# Sheet2.net
KiCad netlist of a schematic drawn in Altium Designer
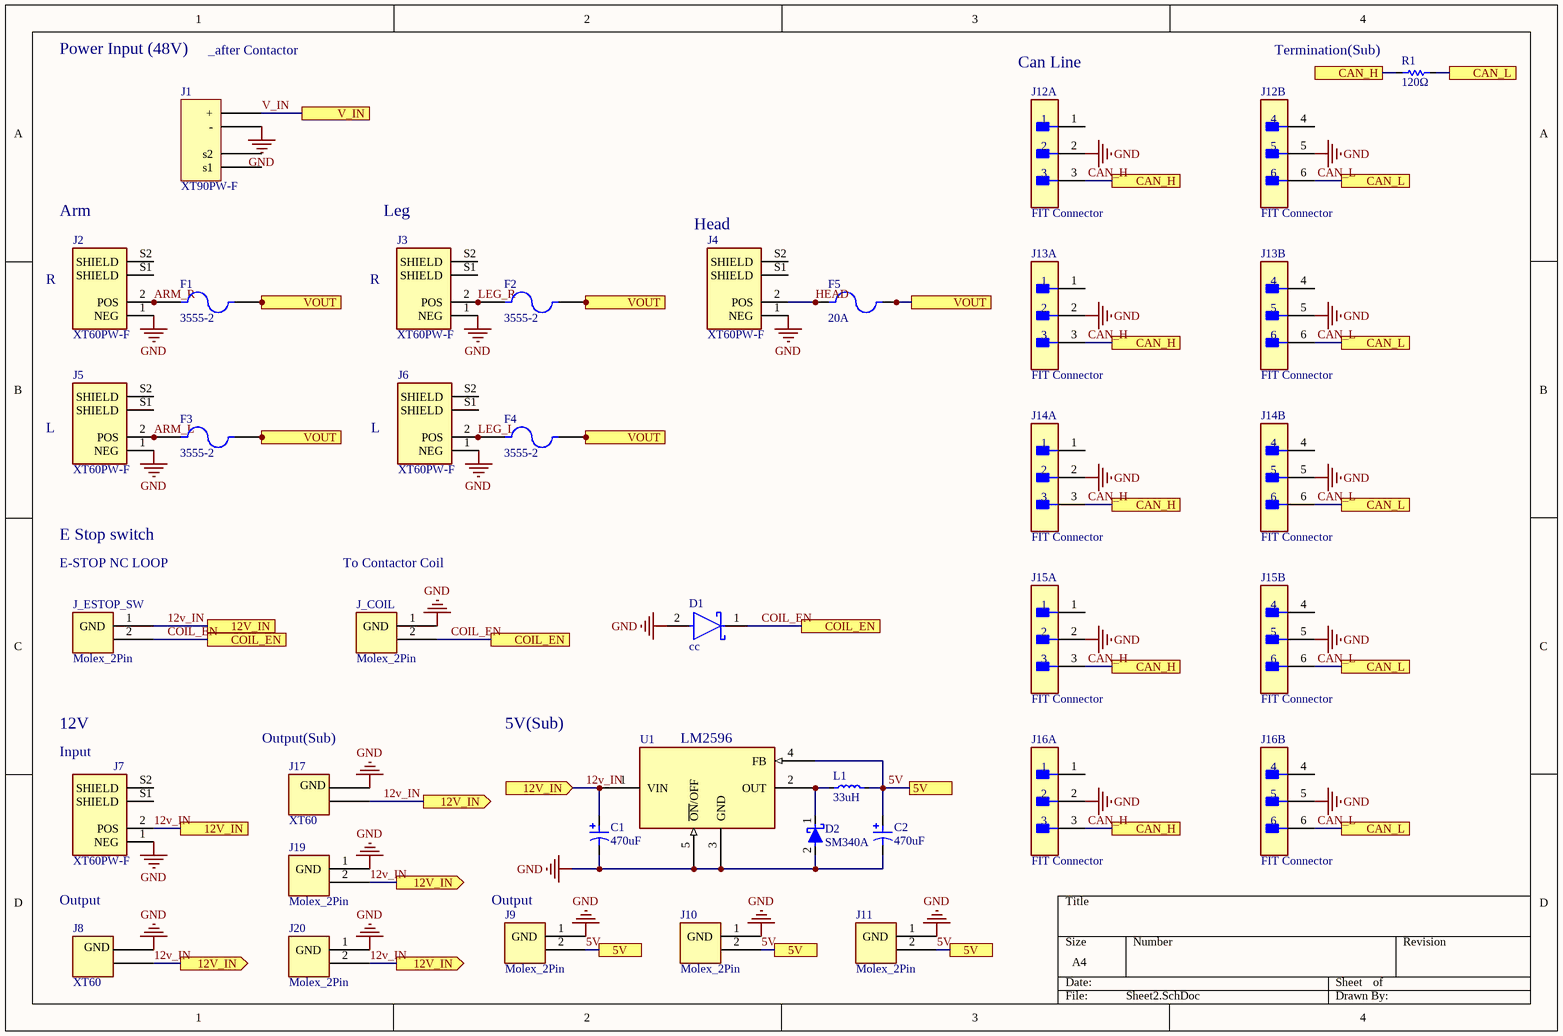
[diagram p0: Sheet2.SchDoc]

(export (version "E")
  (design (tool "Eeschema 10.0.6"))
  (components
    (comp (ref "C1")
      (value "Polar_Capacitors")
      (footprint "SMD_Capacitor_electrolytic")
      (description "Electrolytic Capacitor")
      (fields (field (name "CAPACITANCE") "470uF") (field (name "SOURCE") "robit_passive.SchLib"))
      (libsource (lib "robit circuit") (part "Capacitor_electrolytic"))
    )
    (comp (ref "C2")
      (value "Polar_Capacitors")
      (footprint "SMD_Capacitor_electrolytic")
      (description "Electrolytic Capacitor")
      (fields (field (name "CAPACITANCE") "470uF") (field (name "SOURCE") "robit_passive.SchLib"))
      (libsource (lib "robit circuit") (part "Capacitor_electrolytic"))
    )
    (comp (ref "D1")
      (value "cc")
      (footprint "FP-403A-03-MFG")
      (description "Rectifier Diode, Schottky, 1 Phase, 1 Element, 5A, 100V V(RRM), Silicon")
      (libsource (lib "robit circuit") (part "1d6ec82d83fb6aee721767c19dac4b9"))
    )
    (comp (ref "D2")
      (value "SM340A")
      (footprint "SMD_Diode_schottky")
      (description "Schottky Barrier Diode")
      (fields (field (name "SOURCE") "robit_passive.SchLib"))
      (libsource (lib "robit circuit") (part "Diode_schottky"))
    )
    (comp (ref "F1")
      (value "3555-2")
      (footprint "FUSE_3555-2")
      (fields (field (name "MF") "Keystone Electronics"))
      (libsource (lib "3555-2 (1)") (part "3555-2"))
    )
    (comp (ref "F2")
      (value "3555-2")
      (footprint "FUSE_3555-2")
      (fields (field (name "MF") "Keystone Electronics"))
      (libsource (lib "3555-2 (1)") (part "3555-2"))
    )
    (comp (ref "F3")
      (value "3555-2")
      (footprint "FUSE_3555-2")
      (fields (field (name "MF") "Keystone Electronics"))
      (libsource (lib "3555-2 (1)") (part "3555-2"))
    )
    (comp (ref "F4")
      (value "3555-2")
      (footprint "FUSE_3555-2")
      (fields (field (name "MF") "Keystone Electronics"))
      (libsource (lib "3555-2 (1)") (part "3555-2"))
    )
    (comp (ref "F5")
      (value "20A")
      (footprint "FUSE_CNX-02")
      (description "Fuse Clip for Maxi Blade Fuse, 250VDC/500VAC, 80A")
      (fields (field (name "MF") "OptiFuse") (field (name "MP") "CNX-02"))
      (libsource (lib "robit circuit") (part "CNX-02"))
    )
    (comp (ref "J1")
      (value "XT90PW-F")
      (footprint "AMASS_XT90PW-F")
      (description "Socket, DC supply, XT90, female, PIN:2, on PCBs, THT")
      (fields (field (name "MF") "AMASS"))
      (libsource (lib "robit circuit") (part "XT90PW-F"))
    )
    (comp (ref "J2")
      (value "XT60PW-F")
      (footprint "XT60PW-F")
      (description "Socket DC Supply Connector Female")
      (fields (field (name "MF") "AMASS") (field (name "SOURCE") "robit_connector.SchLib"))
      (libsource (lib "robit circuit") (part "XT60PW-F"))
    )
    (comp (ref "J3")
      (value "XT60PW-F")
      (footprint "XT60PW-F")
      (description "Socket DC Supply Connector Female")
      (fields (field (name "MF") "AMASS") (field (name "SOURCE") "robit_connector.SchLib"))
      (libsource (lib "robit circuit") (part "XT60PW-F"))
    )
    (comp (ref "J4")
      (value "XT60PW-F")
      (footprint "XT60PW-F")
      (description "Socket DC Supply Connector Female")
      (fields (field (name "MF") "AMASS") (field (name "SOURCE") "robit_connector.SchLib"))
      (libsource (lib "robit circuit") (part "XT60PW-F"))
    )
    (comp (ref "J5")
      (value "XT60PW-F")
      (footprint "XT60PW-F")
      (description "Socket DC Supply Connector Female")
      (fields (field (name "MF") "AMASS") (field (name "SOURCE") "robit_connector.SchLib"))
      (libsource (lib "robit circuit") (part "XT60PW-F"))
    )
    (comp (ref "J6")
      (value "XT60PW-F")
      (footprint "XT60PW-F")
      (description "Socket DC Supply Connector Female")
      (fields (field (name "MF") "AMASS") (field (name "SOURCE") "robit_connector.SchLib"))
      (libsource (lib "robit circuit") (part "XT60PW-F"))
    )
    (comp (ref "J7")
      (value "XT60PW-F")
      (footprint "XT60PW-F")
      (description "Socket DC Supply Connector Female")
      (fields (field (name "MF") "AMASS") (field (name "SOURCE") "robit_connector.SchLib"))
      (libsource (lib "robit circuit") (part "XT60PW-F"))
    )
    (comp (ref "J8")
      (value "XT60")
      (footprint "XT60_F")
      (description "XT60 connector")
      (libsource (lib "robit circuit") (part "XT60"))
    )
    (comp (ref "J9")
      (value "Molex_2Pin")
      (footprint "MOLEX_2PIN")
      (description "Molex 2Pin Connector")
      (fields (field (name "SOURCE") "robit_connector.SchLib"))
      (libsource (lib "robit circuit") (part "Molex_2Pin"))
    )
    (comp (ref "J10")
      (value "Molex_2Pin")
      (footprint "MOLEX_2PIN")
      (description "Molex 2Pin Connector")
      (fields (field (name "SOURCE") "robit_connector.SchLib"))
      (libsource (lib "robit circuit") (part "Molex_2Pin"))
    )
    (comp (ref "J11")
      (value "Molex_2Pin")
      (footprint "MOLEX_2PIN")
      (description "Molex 2Pin Connector")
      (fields (field (name "SOURCE") "robit_connector.SchLib"))
      (libsource (lib "robit circuit") (part "Molex_2Pin"))
    )
    (comp (ref "J12")
      (value "FIT Connector")
      (footprint "FP-43045-0601-MFG")
      (description "Connector Wire to Board Header 6 Position 3 mm Solder Right Angle Thru-Hole Micro-Fit 3.0™")
      (libsource (lib "robit circuit") (part "7bb5f7ddfb2bec276e641070710345c"))
    )
    (comp (ref "J13")
      (value "FIT Connector")
      (footprint "FP-43045-0601-MFG")
      (description "Connector Wire to Board Header 6 Position 3 mm Solder Right Angle Thru-Hole Micro-Fit 3.0™")
      (libsource (lib "robit circuit") (part "7bb5f7ddfb2bec276e641070710345c"))
    )
    (comp (ref "J14")
      (value "FIT Connector")
      (footprint "FP-43045-0601-MFG")
      (description "Connector Wire to Board Header 6 Position 3 mm Solder Right Angle Thru-Hole Micro-Fit 3.0™")
      (libsource (lib "robit circuit") (part "7bb5f7ddfb2bec276e641070710345c"))
    )
    (comp (ref "J15")
      (value "FIT Connector")
      (footprint "FP-43045-0601-MFG")
      (description "Connector Wire to Board Header 6 Position 3 mm Solder Right Angle Thru-Hole Micro-Fit 3.0™")
      (libsource (lib "robit circuit") (part "7bb5f7ddfb2bec276e641070710345c"))
    )
    (comp (ref "J16")
      (value "FIT Connector")
      (footprint "FP-43045-0601-MFG")
      (description "Connector Wire to Board Header 6 Position 3 mm Solder Right Angle Thru-Hole Micro-Fit 3.0™")
      (libsource (lib "robit circuit") (part "7bb5f7ddfb2bec276e641070710345c"))
    )
    (comp (ref "J17")
      (value "XT60")
      (footprint "XT60_F")
      (description "XT60 connector")
      (libsource (lib "robit circuit") (part "XT60"))
    )
    (comp (ref "J19")
      (value "Molex_2Pin")
      (footprint "MOLEX_2PIN")
      (description "Molex 2Pin Connector")
      (fields (field (name "SOURCE") "robit_connector.SchLib"))
      (libsource (lib "robit circuit") (part "Molex_2Pin"))
    )
    (comp (ref "J20")
      (value "Molex_2Pin")
      (footprint "MOLEX_2PIN")
      (description "Molex 2Pin Connector")
      (fields (field (name "SOURCE") "robit_connector.SchLib"))
      (libsource (lib "robit circuit") (part "Molex_2Pin"))
    )
    (comp (ref "J_COIL")
      (value "Molex_2Pin")
      (footprint "MOLEX_2PIN")
      (description "Molex 2Pin Connector")
      (fields (field (name "SOURCE") "robit_connector.SchLib"))
      (libsource (lib "robit circuit") (part "Molex_2Pin"))
    )
    (comp (ref "J_ESTOP_SW")
      (value "Molex_2Pin")
      (footprint "MOLEX_2PIN")
      (description "Molex 2Pin Connector")
      (fields (field (name "SOURCE") "robit_connector.SchLib"))
      (libsource (lib "robit circuit") (part "Molex_2Pin"))
    )
    (comp (ref "L1")
      (value "Inductor_Power")
      (footprint "SMD_INDUCTOR_POWER")
      (description "SMD type Inductor")
      (fields (field (name "INDUCTANCE") "33uH") (field (name "SOURCE") "robit_passive.SchLib"))
      (libsource (lib "robit circuit") (part "Inductor_Power"))
    )
    (comp (ref "R1")
      (value "Resistor")
      (footprint "SMD_Resistor")
      (description "SMD type resistor")
      (fields (field (name "RESISTANCE") "120Ω") (field (name "SOURCE") "robit_passive.SchLib"))
      (libsource (lib "robit circuit") (part "Resistor"))
    )
    (comp (ref "U1")
      (value "LM2596")
      (footprint "SMD_LM2596")
      (description "5V Transformer")
      (fields (field (name "SOURCE") "robit_ic.SchLib"))
      (libsource (lib "robit circuit") (part "LM2596"))
    )
  )
  (nets
    (net (code "1") (name "/5V") (class "Default")
      (node (ref "C2") (pin "2") (pinfunction "1_2") (pintype "passive"))
      (node (ref "J10") (pin "2") (pintype "passive"))
      (node (ref "J11") (pin "2") (pintype "passive"))
      (node (ref "J9") (pin "2") (pintype "passive"))
      (node (ref "L1") (pin "2") (pintype "passive"))
      (node (ref "U1") (pin "4") (pinfunction "FB_4") (pintype "input"))
    )
    (net (code "2") (name "/12v_IN") (class "Default")
      (node (ref "C1") (pin "2") (pinfunction "1_2") (pintype "passive"))
      (node (ref "J17") (pin "2") (pinfunction "2_2") (pintype "passive"))
      (node (ref "J19") (pin "2") (pintype "passive"))
      (node (ref "J20") (pin "2") (pintype "passive"))
      (node (ref "J7") (pin "2") (pinfunction "POS_2") (pintype "passive"))
      (node (ref "J8") (pin "2") (pinfunction "2_2") (pintype "passive"))
      (node (ref "J_ESTOP_SW") (pin "1") (pinfunction "GND_1") (pintype "passive"))
      (node (ref "U1") (pin "1") (pinfunction "VIN_1") (pintype "power_in"))
    )
    (net (code "3") (name "/ARM_L") (class "Default")
      (node (ref "F3") (pin "1_1") (pinfunction "1_1_1") (pintype "passive"))
      (node (ref "F3") (pin "1_2") (pinfunction "1_1_2") (pintype "passive"))
      (node (ref "J5") (pin "2") (pinfunction "POS_2") (pintype "passive"))
    )
    (net (code "4") (name "/ARM_R") (class "Default")
      (node (ref "F1") (pin "1_1") (pinfunction "1_1_1") (pintype "passive"))
      (node (ref "F1") (pin "1_2") (pinfunction "1_1_2") (pintype "passive"))
      (node (ref "J2") (pin "2") (pinfunction "POS_2") (pintype "passive"))
    )
    (net (code "5") (name "/CAN_H") (class "Default")
      (node (ref "J12") (pin "3") (pinfunction "3_3") (pintype "passive"))
      (node (ref "J13") (pin "3") (pinfunction "3_3") (pintype "passive"))
      (node (ref "J14") (pin "3") (pinfunction "3_3") (pintype "passive"))
      (node (ref "J15") (pin "3") (pinfunction "3_3") (pintype "passive"))
      (node (ref "J16") (pin "3") (pinfunction "3_3") (pintype "passive"))
      (node (ref "R1") (pin "1") (pinfunction "1_1") (pintype "passive"))
    )
    (net (code "6") (name "/CAN_L") (class "Default")
      (node (ref "J12") (pin "6") (pinfunction "6_6") (pintype "passive"))
      (node (ref "J13") (pin "6") (pinfunction "6_6") (pintype "passive"))
      (node (ref "J14") (pin "6") (pinfunction "6_6") (pintype "passive"))
      (node (ref "J15") (pin "6") (pinfunction "6_6") (pintype "passive"))
      (node (ref "J16") (pin "6") (pinfunction "6_6") (pintype "passive"))
      (node (ref "R1") (pin "2") (pinfunction "2_2") (pintype "passive"))
    )
    (net (code "7") (name "/COIL_EN") (class "Default")
      (node (ref "D1") (pin "1") (pinfunction "C_1") (pintype "passive"))
      (node (ref "J_COIL") (pin "2") (pintype "passive"))
      (node (ref "J_ESTOP_SW") (pin "2") (pintype "passive"))
    )
    (net (code "8") (name "/HEAD") (class "Default")
      (node (ref "F5") (pin "1_1") (pinfunction "1_1_1") (pintype "passive"))
      (node (ref "F5") (pin "1_2") (pinfunction "1_1_2") (pintype "passive"))
      (node (ref "J4") (pin "2") (pinfunction "POS_2") (pintype "passive"))
    )
    (net (code "9") (name "/LEG_L") (class "Default")
      (node (ref "F4") (pin "1_1") (pinfunction "1_1_1") (pintype "passive"))
      (node (ref "F4") (pin "1_2") (pinfunction "1_1_2") (pintype "passive"))
      (node (ref "J6") (pin "2") (pinfunction "POS_2") (pintype "passive"))
    )
    (net (code "10") (name "/LEG_R") (class "Default")
      (node (ref "F2") (pin "1_1") (pinfunction "1_1_1") (pintype "passive"))
      (node (ref "F2") (pin "1_2") (pinfunction "1_1_2") (pintype "passive"))
      (node (ref "J3") (pin "2") (pinfunction "POS_2") (pintype "passive"))
    )
    (net (code "11") (name "/VOUT") (class "Default")
      (node (ref "F1") (pin "2_1") (pinfunction "2_2_1") (pintype "passive"))
      (node (ref "F1") (pin "2_2") (pinfunction "2_2_2") (pintype "passive"))
      (node (ref "F2") (pin "2_1") (pinfunction "2_2_1") (pintype "passive"))
      (node (ref "F2") (pin "2_2") (pinfunction "2_2_2") (pintype "passive"))
      (node (ref "F3") (pin "2_1") (pinfunction "2_2_1") (pintype "passive"))
      (node (ref "F3") (pin "2_2") (pinfunction "2_2_2") (pintype "passive"))
      (node (ref "F4") (pin "2_1") (pinfunction "2_2_1") (pintype "passive"))
      (node (ref "F4") (pin "2_2") (pinfunction "2_2_2") (pintype "passive"))
      (node (ref "F5") (pin "2_1") (pinfunction "2_2_1") (pintype "passive"))
      (node (ref "F5") (pin "2_2") (pinfunction "2_2_2") (pintype "passive"))
    )
    (net (code "12") (name "/V_IN") (class "Default")
      (node (ref "J1") (pin "P") (pinfunction "+_P") (pintype "power_in"))
    )
    (net (code "13") (name "GND") (class "Default")
      (node (ref "C1") (pin "1") (pinfunction "0_1") (pintype "passive"))
      (node (ref "C2") (pin "1") (pinfunction "0_1") (pintype "passive"))
      (node (ref "D1") (pin "2") (pinfunction "A_2") (pintype "passive"))
      (node (ref "D2") (pin "2") (pintype "passive"))
      (node (ref "J1") (pin "N") (pinfunction "-_N") (pintype "power_in"))
      (node (ref "J10") (pin "1") (pinfunction "GND_1") (pintype "passive"))
      (node (ref "J11") (pin "1") (pinfunction "GND_1") (pintype "passive"))
      (node (ref "J12") (pin "2") (pinfunction "2_2") (pintype "passive"))
      (node (ref "J12") (pin "5") (pinfunction "5_5") (pintype "passive"))
      (node (ref "J13") (pin "2") (pinfunction "2_2") (pintype "passive"))
      (node (ref "J13") (pin "5") (pinfunction "5_5") (pintype "passive"))
      (node (ref "J14") (pin "2") (pinfunction "2_2") (pintype "passive"))
      (node (ref "J14") (pin "5") (pinfunction "5_5") (pintype "passive"))
      (node (ref "J15") (pin "2") (pinfunction "2_2") (pintype "passive"))
      (node (ref "J15") (pin "5") (pinfunction "5_5") (pintype "passive"))
      (node (ref "J16") (pin "2") (pinfunction "2_2") (pintype "passive"))
      (node (ref "J16") (pin "5") (pinfunction "5_5") (pintype "passive"))
      (node (ref "J17") (pin "1") (pinfunction "1_1") (pintype "passive"))
      (node (ref "J19") (pin "1") (pinfunction "GND_1") (pintype "passive"))
      (node (ref "J2") (pin "1") (pinfunction "NEG_1") (pintype "passive"))
      (node (ref "J20") (pin "1") (pinfunction "GND_1") (pintype "passive"))
      (node (ref "J3") (pin "1") (pinfunction "NEG_1") (pintype "passive"))
      (node (ref "J4") (pin "1") (pinfunction "NEG_1") (pintype "passive"))
      (node (ref "J5") (pin "1") (pinfunction "NEG_1") (pintype "passive"))
      (node (ref "J6") (pin "1") (pinfunction "NEG_1") (pintype "passive"))
      (node (ref "J7") (pin "1") (pinfunction "NEG_1") (pintype "passive"))
      (node (ref "J8") (pin "1") (pinfunction "1_1") (pintype "passive"))
      (node (ref "J9") (pin "1") (pinfunction "GND_1") (pintype "passive"))
      (node (ref "J_COIL") (pin "1") (pinfunction "GND_1") (pintype "passive"))
      (node (ref "U1") (pin "3") (pinfunction "GND_3") (pintype "power_in"))
      (node (ref "U1") (pin "5") (pinfunction "~{ON}/OFF_5") (pintype "input"))
    )
    (net (code "14") (name "Net-(U1-OUT)") (class "Default")
      (node (ref "D2") (pin "1") (pintype "passive"))
      (node (ref "L1") (pin "1") (pintype "passive"))
      (node (ref "U1") (pin "2") (pinfunction "OUT_2") (pintype "power_in"))
    )
    (net (code "15") (name "unconnected-(J1-s1-PadS1)") (class "Default")
      (node (ref "J1") (pin "S1") (pinfunction "s1_S1") (pintype "power_in"))
    )
    (net (code "16") (name "unconnected-(J1-s2-PadS2)") (class "Default")
      (node (ref "J1") (pin "S2") (pinfunction "s2_S2") (pintype "power_in"))
    )
    (net (code "17") (name "unconnected-(J2-SHIELD-PadS1)") (class "Default")
      (node (ref "J2") (pin "S1") (pinfunction "SHIELD_S1") (pintype "passive"))
    )
    (net (code "18") (name "unconnected-(J2-SHIELD-PadS2)") (class "Default")
      (node (ref "J2") (pin "S2") (pinfunction "SHIELD_S2") (pintype "passive"))
    )
    (net (code "19") (name "unconnected-(J3-SHIELD-PadS1)") (class "Default")
      (node (ref "J3") (pin "S1") (pinfunction "SHIELD_S1") (pintype "passive"))
    )
    (net (code "20") (name "unconnected-(J3-SHIELD-PadS2)") (class "Default")
      (node (ref "J3") (pin "S2") (pinfunction "SHIELD_S2") (pintype "passive"))
    )
    (net (code "21") (name "unconnected-(J4-SHIELD-PadS1)") (class "Default")
      (node (ref "J4") (pin "S1") (pinfunction "SHIELD_S1") (pintype "passive"))
    )
    (net (code "22") (name "unconnected-(J4-SHIELD-PadS2)") (class "Default")
      (node (ref "J4") (pin "S2") (pinfunction "SHIELD_S2") (pintype "passive"))
    )
    (net (code "23") (name "unconnected-(J5-SHIELD-PadS1)") (class "Default")
      (node (ref "J5") (pin "S1") (pinfunction "SHIELD_S1") (pintype "passive"))
    )
    (net (code "24") (name "unconnected-(J5-SHIELD-PadS2)") (class "Default")
      (node (ref "J5") (pin "S2") (pinfunction "SHIELD_S2") (pintype "passive"))
    )
    (net (code "25") (name "unconnected-(J6-SHIELD-PadS1)") (class "Default")
      (node (ref "J6") (pin "S1") (pinfunction "SHIELD_S1") (pintype "passive"))
    )
    (net (code "26") (name "unconnected-(J6-SHIELD-PadS2)") (class "Default")
      (node (ref "J6") (pin "S2") (pinfunction "SHIELD_S2") (pintype "passive"))
    )
    (net (code "27") (name "unconnected-(J7-SHIELD-PadS1)") (class "Default")
      (node (ref "J7") (pin "S1") (pinfunction "SHIELD_S1") (pintype "passive"))
    )
    (net (code "28") (name "unconnected-(J7-SHIELD-PadS2)") (class "Default")
      (node (ref "J7") (pin "S2") (pinfunction "SHIELD_S2") (pintype "passive"))
    )
    (net (code "29") (name "unconnected-(J12-Pad1)") (class "Default")
      (node (ref "J12") (pin "1") (pinfunction "1_1") (pintype "passive"))
    )
    (net (code "30") (name "unconnected-(J12-Pad4)") (class "Default")
      (node (ref "J12") (pin "4") (pinfunction "4_4") (pintype "passive"))
    )
    (net (code "31") (name "unconnected-(J13-Pad1)") (class "Default")
      (node (ref "J13") (pin "1") (pinfunction "1_1") (pintype "passive"))
    )
    (net (code "32") (name "unconnected-(J13-Pad4)") (class "Default")
      (node (ref "J13") (pin "4") (pinfunction "4_4") (pintype "passive"))
    )
    (net (code "33") (name "unconnected-(J14-Pad1)") (class "Default")
      (node (ref "J14") (pin "1") (pinfunction "1_1") (pintype "passive"))
    )
    (net (code "34") (name "unconnected-(J14-Pad4)") (class "Default")
      (node (ref "J14") (pin "4") (pinfunction "4_4") (pintype "passive"))
    )
    (net (code "35") (name "unconnected-(J15-Pad1)") (class "Default")
      (node (ref "J15") (pin "1") (pinfunction "1_1") (pintype "passive"))
    )
    (net (code "36") (name "unconnected-(J15-Pad4)") (class "Default")
      (node (ref "J15") (pin "4") (pinfunction "4_4") (pintype "passive"))
    )
    (net (code "37") (name "unconnected-(J16-Pad1)") (class "Default")
      (node (ref "J16") (pin "1") (pinfunction "1_1") (pintype "passive"))
    )
    (net (code "38") (name "unconnected-(J16-Pad4)") (class "Default")
      (node (ref "J16") (pin "4") (pinfunction "4_4") (pintype "passive"))
    )
  )
)
